# 2-Lead_ECG.net
KiCad netlist of a schematic drawn in EAGLE
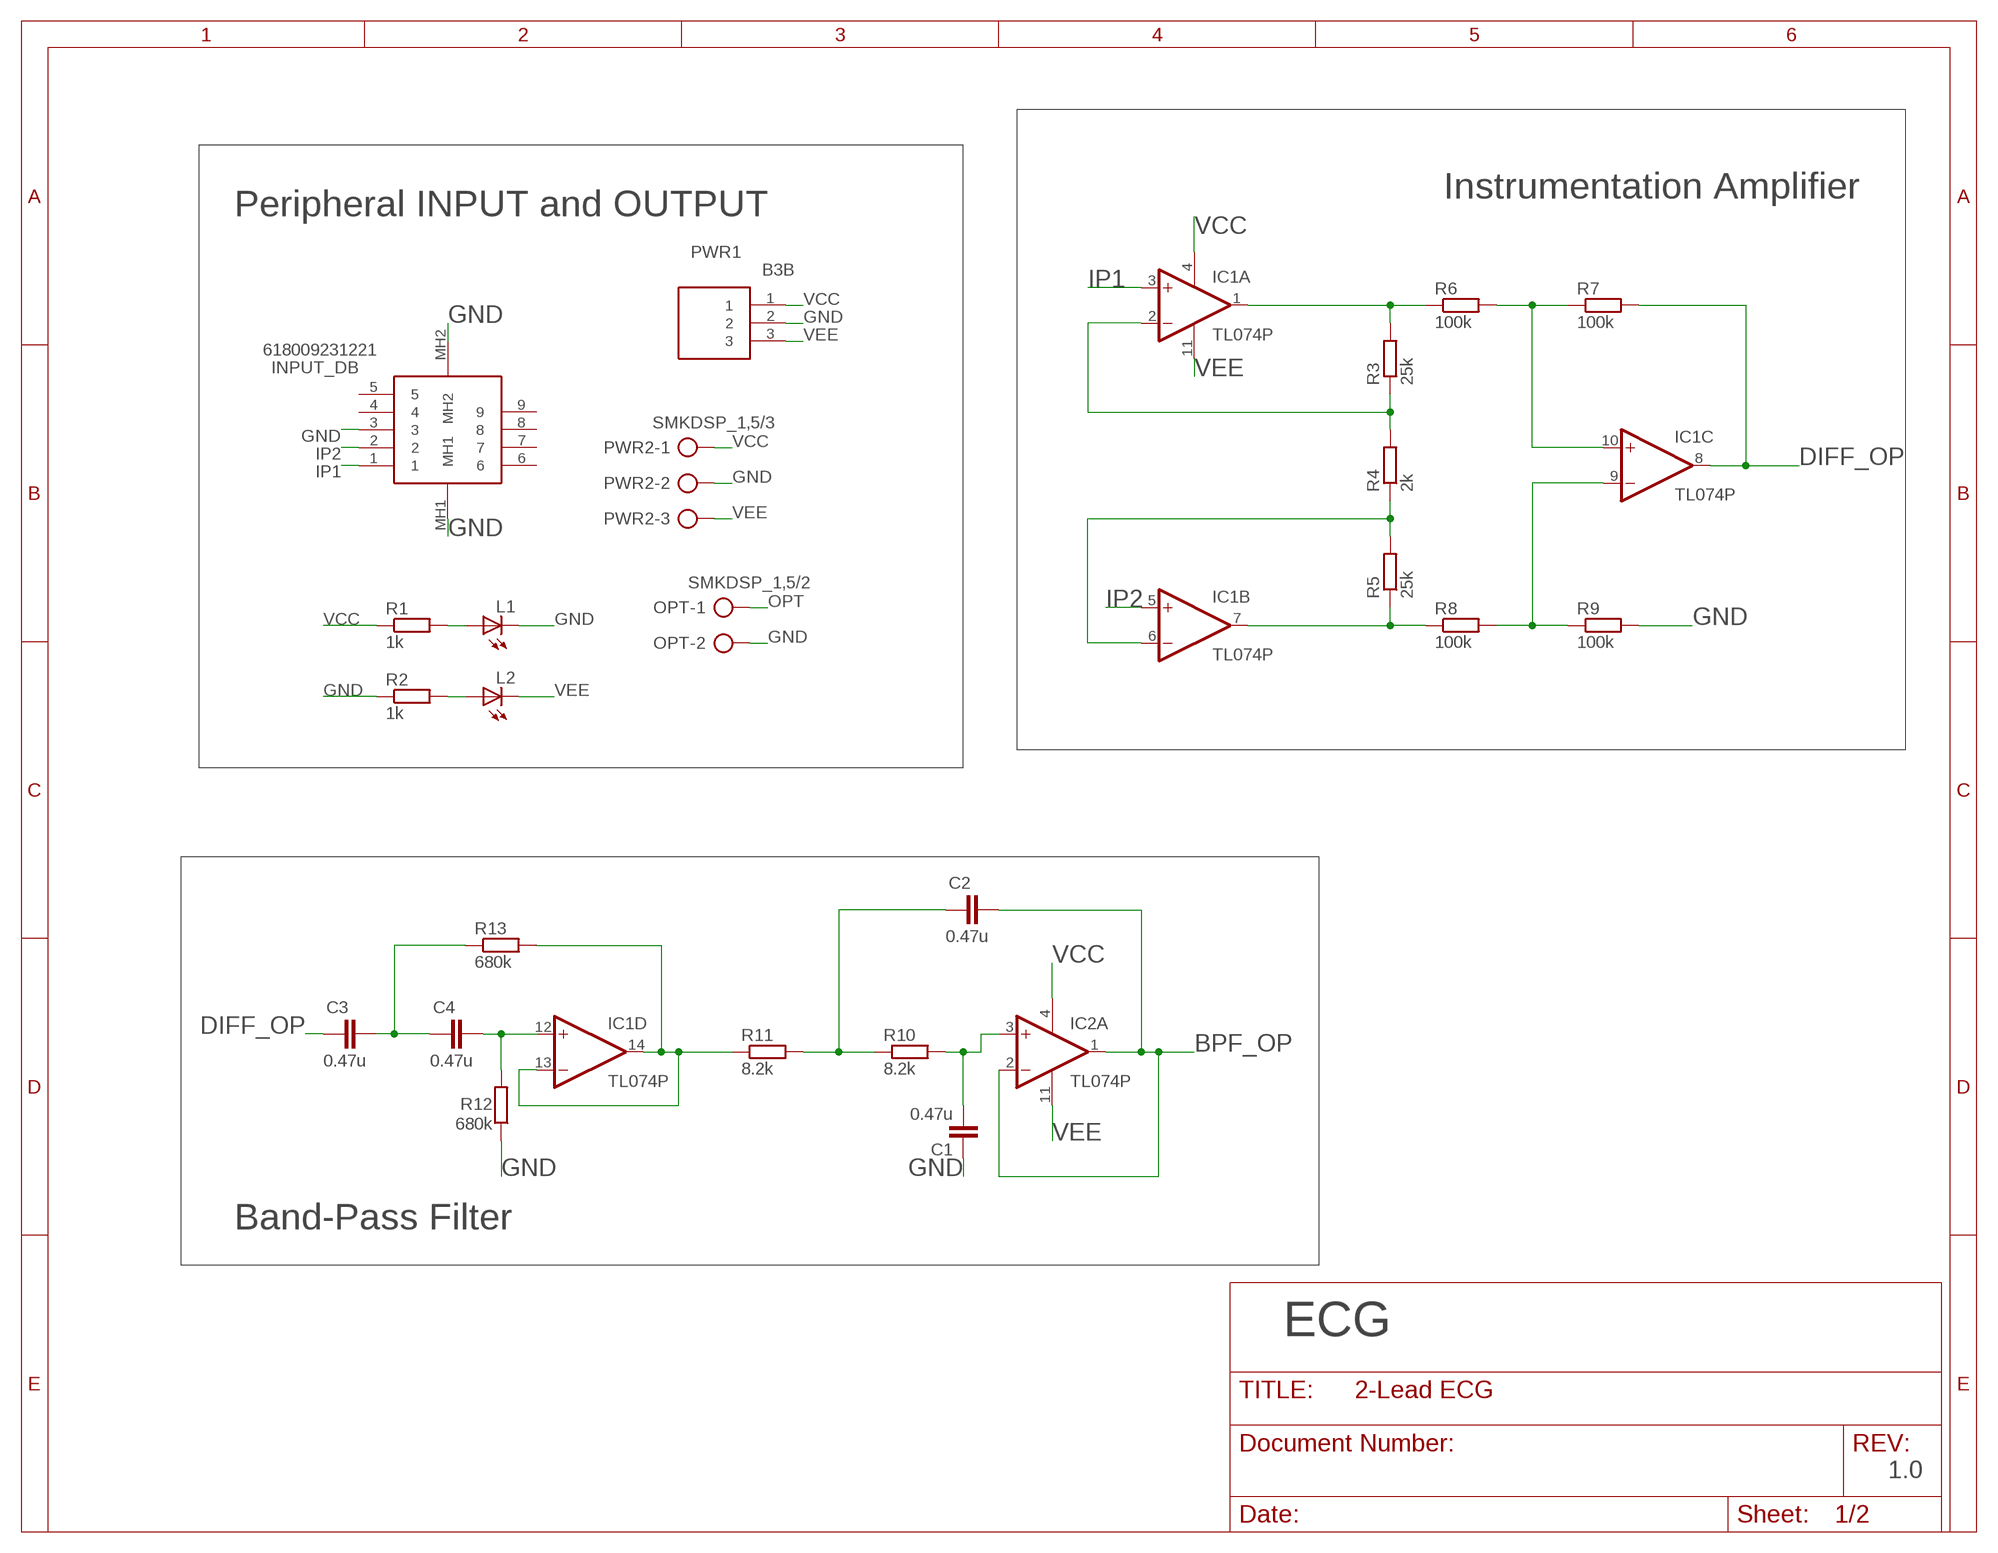
[diagram p0: schematic, sheet 1]
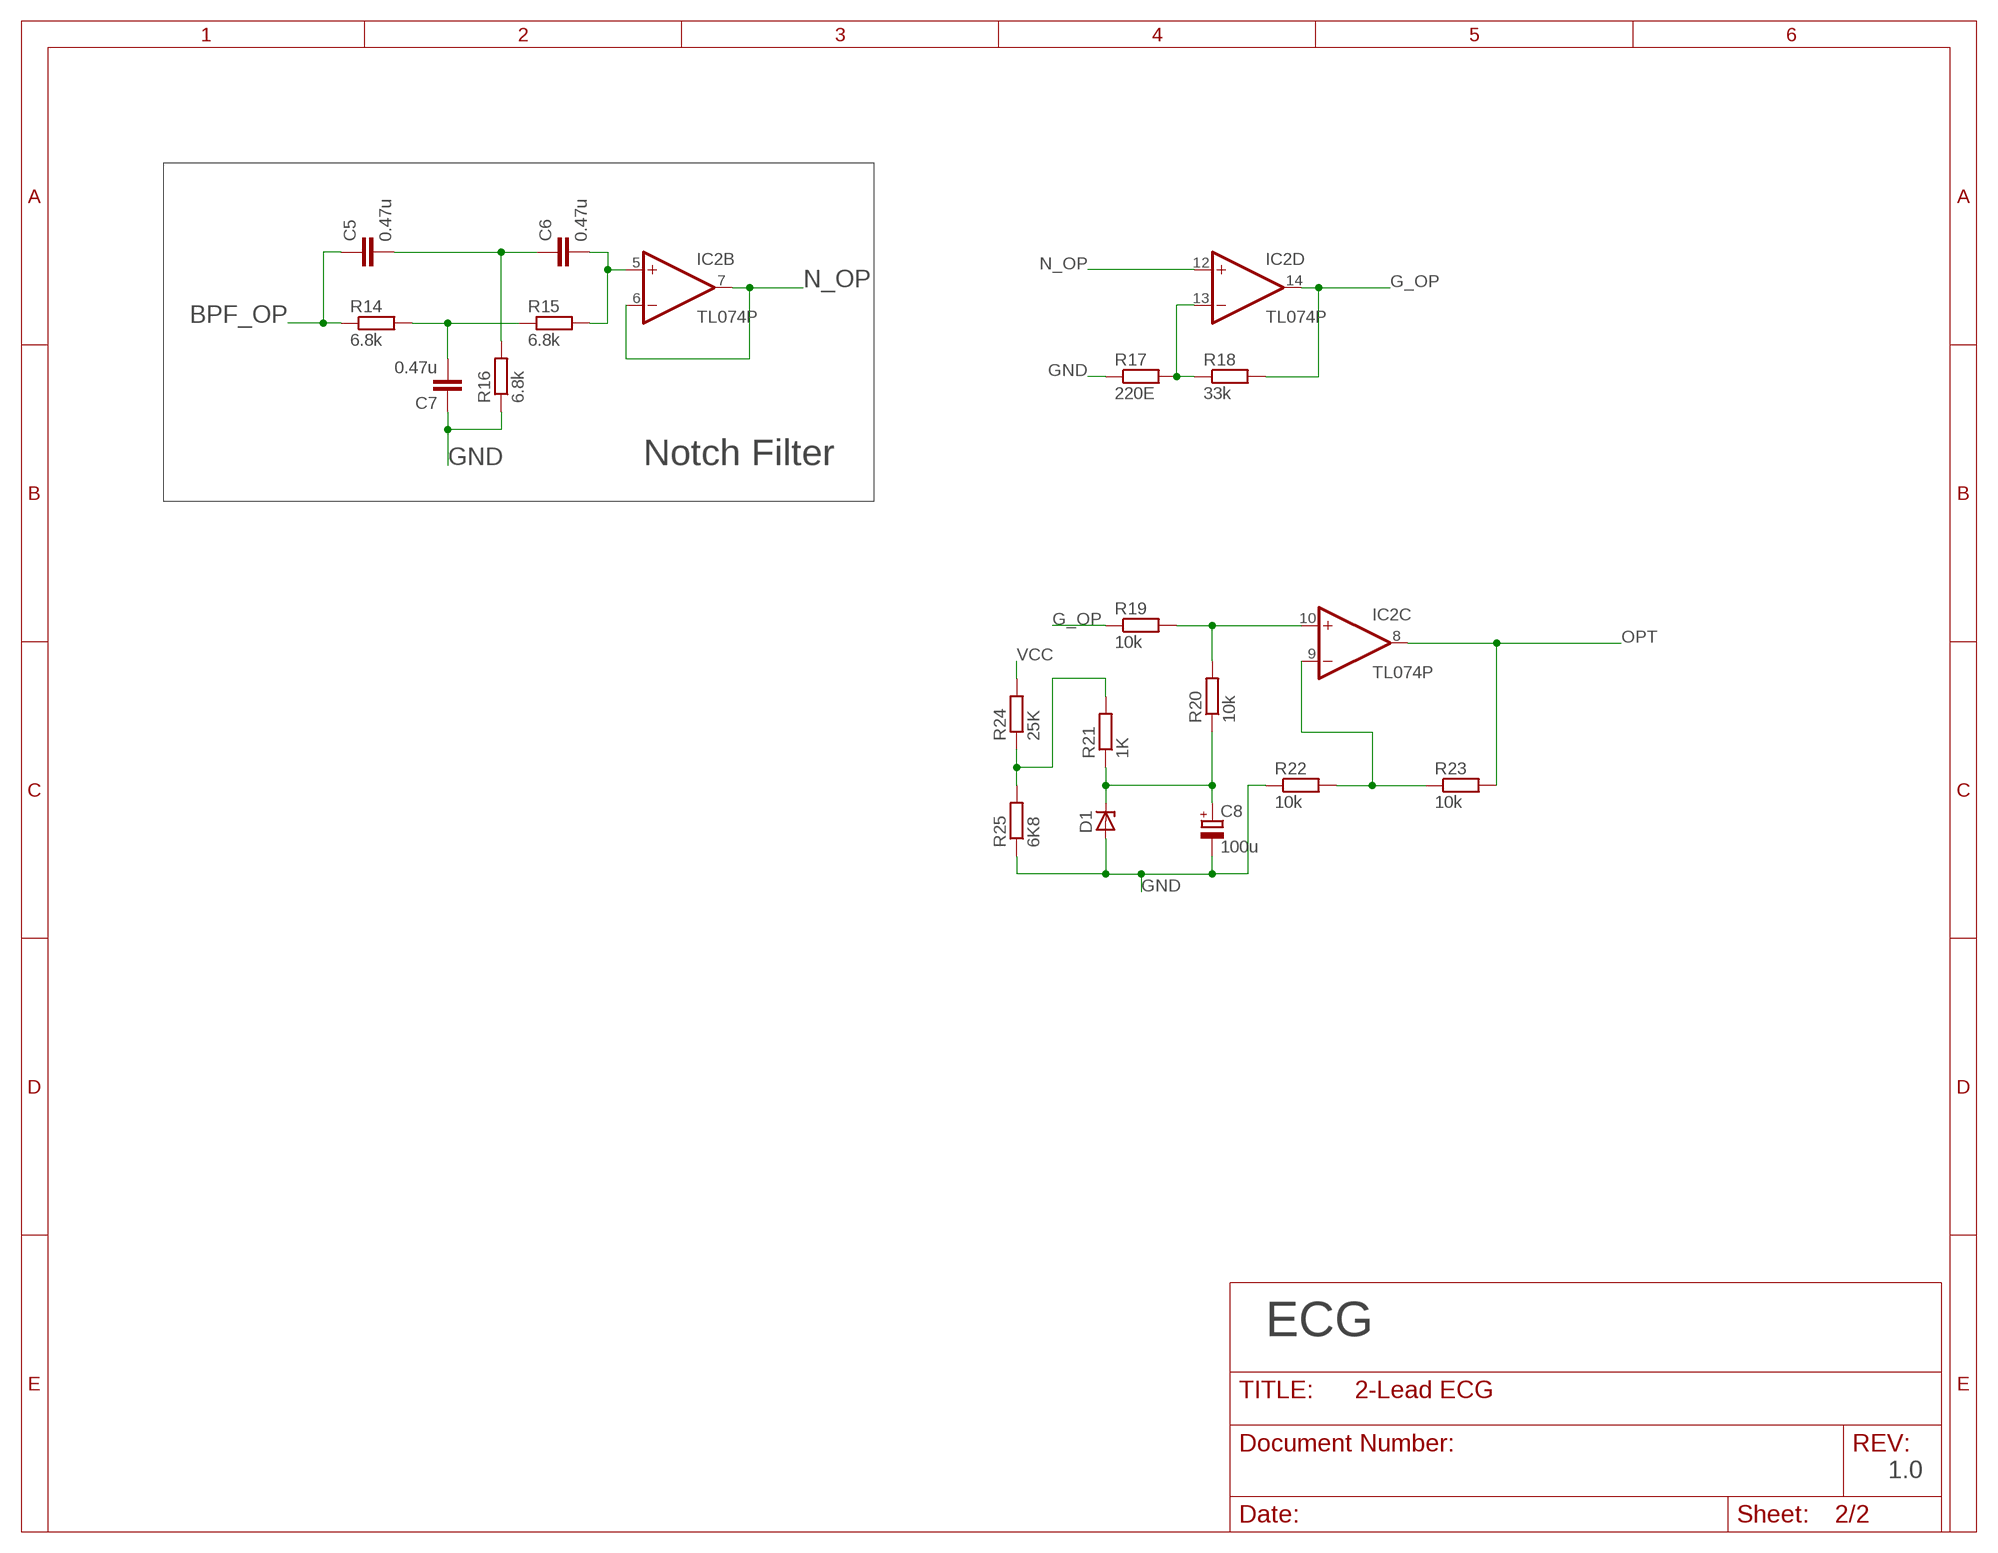
[diagram p1: schematic, sheet 2]

(export (version "E")
  (design (tool "Eeschema 10.0.6"))
  (components
    (comp (ref "C1")
      (value "0.47u")
      (footprint "eagle-import:C050-025X075")
      (libsource (lib "eagle-import") (part "C-EU050-025X075"))
    )
    (comp (ref "C2")
      (value "0.47u")
      (footprint "eagle-import:C050-025X075")
      (libsource (lib "eagle-import") (part "C-EU050-025X075"))
    )
    (comp (ref "C3")
      (value "0.47u")
      (footprint "eagle-import:C050-025X075")
      (libsource (lib "eagle-import") (part "C-EU050-025X075"))
    )
    (comp (ref "C4")
      (value "0.47u")
      (footprint "eagle-import:C050-025X075")
      (libsource (lib "eagle-import") (part "C-EU050-025X075"))
    )
    (comp (ref "IC1")
      (value "TL074P")
      (footprint "eagle-import:DIL14")
      (libsource (lib "eagle-import") (part "TL074P"))
    )
    (comp (ref "IC2")
      (value "TL074P")
      (footprint "eagle-import:DIL14")
      (libsource (lib "eagle-import") (part "TL074P"))
    )
    (comp (ref "INPUT_DB")
      (value "618009231221")
      (footprint "eagle-import:618009231221")
      (fields (field (name "MOUSER_PART_NUMBER") "710-618009231221"))
      (libsource (lib "eagle-import") (part "618009231221"))
    )
    (comp (ref "L1")
      (value "LED3MM")
      (footprint "eagle-import:LED3MM")
      (libsource (lib "eagle-import") (part "LED3MM"))
    )
    (comp (ref "L2")
      (value "LED3MM")
      (footprint "eagle-import:LED3MM")
      (libsource (lib "eagle-import") (part "LED3MM"))
    )
    (comp (ref "OPT")
      (value "SMKDSP_1,5/2")
      (footprint "eagle-import:SMKDSP_1,5_2")
      (fields (field (name "MF") "FARNELL") (field (name "MPN") "1733570"))
      (libsource (lib "eagle-import") (part "SMKDSP_1,5/2"))
    )
    (comp (ref "PWR1")
      (value "B3B")
      (footprint "eagle-import:SHDR3W64P0X250_1X3_1000X380X60")
      (fields (field (name "ARROW_PART_NUMBER") "B3B-EH-A (LF) (SN)"))
      (libsource (lib "eagle-import") (part "B3B-EH-A__LF___SN_"))
    )
    (comp (ref "PWR2")
      (value "SMKDSP_1,5/3")
      (footprint "eagle-import:SMKDSP_1,5_3")
      (fields (field (name "MF") "FARNELL") (field (name "MPN") "1733583"))
      (libsource (lib "eagle-import") (part "SMKDSP_1,5/3"))
    )
    (comp (ref "R1")
      (value "1k")
      (footprint "eagle-import:0207_10")
      (libsource (lib "eagle-import") (part "R-EU_0207/10"))
    )
    (comp (ref "R2")
      (value "1k")
      (footprint "eagle-import:0207_10")
      (libsource (lib "eagle-import") (part "R-EU_0207/10"))
    )
    (comp (ref "R3")
      (value "25k")
      (footprint "eagle-import:0204V")
      (libsource (lib "eagle-import") (part "R-EU_0204/2V"))
    )
    (comp (ref "R4")
      (value "2k")
      (footprint "eagle-import:0207_10")
      (libsource (lib "eagle-import") (part "R-EU_0207/10"))
    )
    (comp (ref "R5")
      (value "25k")
      (footprint "eagle-import:0204V")
      (libsource (lib "eagle-import") (part "R-EU_0204/2V"))
    )
    (comp (ref "R6")
      (value "100k")
      (footprint "eagle-import:0207_10")
      (libsource (lib "eagle-import") (part "R-EU_0207/10"))
    )
    (comp (ref "R7")
      (value "100k")
      (footprint "eagle-import:0207_10")
      (libsource (lib "eagle-import") (part "R-EU_0207/10"))
    )
    (comp (ref "R8")
      (value "100k")
      (footprint "eagle-import:0207_10")
      (libsource (lib "eagle-import") (part "R-EU_0207/10"))
    )
    (comp (ref "R9")
      (value "100k")
      (footprint "eagle-import:0207_10")
      (libsource (lib "eagle-import") (part "R-EU_0207/10"))
    )
    (comp (ref "R10")
      (value "8.2k")
      (footprint "eagle-import:0207_10")
      (libsource (lib "eagle-import") (part "R-EU_0207/10"))
    )
    (comp (ref "R11")
      (value "8.2k")
      (footprint "eagle-import:0207_10")
      (libsource (lib "eagle-import") (part "R-EU_0207/10"))
    )
    (comp (ref "R12")
      (value "680k")
      (footprint "eagle-import:0207_10")
      (libsource (lib "eagle-import") (part "R-EU_0207/10"))
    )
    (comp (ref "R13")
      (value "680k")
      (footprint "eagle-import:0207_10")
      (libsource (lib "eagle-import") (part "R-EU_0207/10"))
    )
    (comp (ref "C5")
      (value "0.47u")
      (footprint "eagle-import:C050-025X075")
      (libsource (lib "eagle-import") (part "C-EU050-025X075"))
    )
    (comp (ref "C6")
      (value "0.47u")
      (footprint "eagle-import:C050-025X075")
      (libsource (lib "eagle-import") (part "C-EU050-025X075"))
    )
    (comp (ref "C7")
      (value "0.47u")
      (footprint "eagle-import:C050-025X075")
      (libsource (lib "eagle-import") (part "C-EU050-025X075"))
    )
    (comp (ref "C8")
      (value "100u")
      (footprint "eagle-import:E2,5-5")
      (libsource (lib "eagle-import") (part "CPOL-EUE2.5-5"))
    )
    (comp (ref "D1")
      (value "ZENER-DIODEC1702-15")
      (footprint "eagle-import:C1702-15")
      (libsource (lib "eagle-import") (part "ZENER-DIODEC1702-15"))
    )
    (comp (ref "R14")
      (value "6.8k")
      (footprint "eagle-import:0207_10")
      (libsource (lib "eagle-import") (part "R-EU_0207/10"))
    )
    (comp (ref "R15")
      (value "6.8k")
      (footprint "eagle-import:0207_10")
      (libsource (lib "eagle-import") (part "R-EU_0207/10"))
    )
    (comp (ref "R16")
      (value "6.8k")
      (footprint "eagle-import:0207_10")
      (libsource (lib "eagle-import") (part "R-EU_0207/10"))
    )
    (comp (ref "R17")
      (value "220E")
      (footprint "eagle-import:0204V")
      (libsource (lib "eagle-import") (part "R-EU_0204/2V"))
    )
    (comp (ref "R18")
      (value "33k")
      (footprint "eagle-import:0204V")
      (libsource (lib "eagle-import") (part "R-EU_0204/2V"))
    )
    (comp (ref "R19")
      (value "10k")
      (footprint "eagle-import:0204V")
      (libsource (lib "eagle-import") (part "R-EU_0204/2V"))
    )
    (comp (ref "R20")
      (value "10k")
      (footprint "eagle-import:0204V")
      (libsource (lib "eagle-import") (part "R-EU_0204/2V"))
    )
    (comp (ref "R21")
      (value "1K")
      (footprint "eagle-import:0207_10")
      (libsource (lib "eagle-import") (part "R-EU_0207/10"))
    )
    (comp (ref "R22")
      (value "10k")
      (footprint "eagle-import:0204V")
      (libsource (lib "eagle-import") (part "R-EU_0204/2V"))
    )
    (comp (ref "R23")
      (value "10k")
      (footprint "eagle-import:0204V")
      (libsource (lib "eagle-import") (part "R-EU_0204/2V"))
    )
    (comp (ref "R24")
      (value "25K")
      (footprint "eagle-import:0207_10")
      (libsource (lib "eagle-import") (part "R-EU_0207/10"))
    )
    (comp (ref "R25")
      (value "6K8")
      (footprint "eagle-import:0207_10")
      (libsource (lib "eagle-import") (part "R-EU_0207/10"))
    )
  )
  (nets
    (net (code "1") (name "BPF_OP") (class "Default")
      (node (ref "C2") (pin "2") (pinfunction "2_2") (pintype "passive"))
      (node (ref "C5") (pin "1") (pinfunction "1_1") (pintype "passive"))
      (node (ref "IC2") (pin "1") (pinfunction "OUT_1") (pintype "output"))
      (node (ref "IC2") (pin "2") (pinfunction "-IN_2") (pintype "input"))
      (node (ref "R14") (pin "1") (pinfunction "1_1") (pintype "passive"))
    )
    (net (code "2") (name "DIFF_OP") (class "Default")
      (node (ref "C3") (pin "1") (pinfunction "1_1") (pintype "passive"))
      (node (ref "IC1") (pin "8") (pinfunction "OUT_8") (pintype "output"))
      (node (ref "R7") (pin "2") (pinfunction "2_2") (pintype "passive"))
    )
    (net (code "3") (name "GND") (class "Default")
      (node (ref "C1") (pin "1") (pinfunction "1_1") (pintype "passive"))
      (node (ref "C7") (pin "1") (pinfunction "1_1") (pintype "passive"))
      (node (ref "C8") (pin "-") (pinfunction "-_-") (pintype "passive"))
      (node (ref "D1") (pin "A") (pinfunction "A_A") (pintype "passive"))
      (node (ref "INPUT_DB") (pin "3") (pinfunction "3_3") (pintype "bidirectional"))
      (node (ref "INPUT_DB") (pin "MH1") (pinfunction "MH1_MH1") (pintype "bidirectional"))
      (node (ref "INPUT_DB") (pin "MH2") (pinfunction "MH2_MH2") (pintype "bidirectional"))
      (node (ref "L1") (pin "K") (pinfunction "C_K") (pintype "passive"))
      (node (ref "OPT") (pin "2") (pinfunction "KL_2") (pintype "passive"))
      (node (ref "PWR1") (pin "2") (pinfunction "2_2") (pintype "bidirectional"))
      (node (ref "PWR2") (pin "2") (pinfunction "KL_2") (pintype "passive"))
      (node (ref "R12") (pin "1") (pinfunction "1_1") (pintype "passive"))
      (node (ref "R16") (pin "1") (pinfunction "1_1") (pintype "passive"))
      (node (ref "R17") (pin "1") (pinfunction "1_1") (pintype "passive"))
      (node (ref "R2") (pin "1") (pinfunction "1_1") (pintype "passive"))
      (node (ref "R22") (pin "1") (pinfunction "1_1") (pintype "passive"))
      (node (ref "R25") (pin "1") (pinfunction "1_1") (pintype "passive"))
      (node (ref "R9") (pin "2") (pinfunction "2_2") (pintype "passive"))
    )
    (net (code "4") (name "G_OP") (class "Default")
      (node (ref "IC2") (pin "14") (pinfunction "OUT_14") (pintype "output"))
      (node (ref "R18") (pin "2") (pinfunction "2_2") (pintype "passive"))
      (node (ref "R19") (pin "1") (pinfunction "1_1") (pintype "passive"))
    )
    (net (code "5") (name "IP1") (class "Default")
      (node (ref "IC1") (pin "3") (pinfunction "+IN_3") (pintype "input"))
      (node (ref "INPUT_DB") (pin "1") (pinfunction "1_1") (pintype "bidirectional"))
    )
    (net (code "6") (name "IP2") (class "Default")
      (node (ref "IC1") (pin "5") (pinfunction "+IN_5") (pintype "input"))
      (node (ref "INPUT_DB") (pin "2") (pinfunction "2_2") (pintype "bidirectional"))
    )
    (net (code "7") (name "N_OP") (class "Default")
      (node (ref "IC2") (pin "12") (pinfunction "+IN_12") (pintype "input"))
      (node (ref "IC2") (pin "6") (pinfunction "-IN_6") (pintype "input"))
      (node (ref "IC2") (pin "7") (pinfunction "OUT_7") (pintype "output"))
    )
    (net (code "8") (name "Net-(C2-Pad1)") (class "Default")
      (node (ref "C2") (pin "1") (pinfunction "1_1") (pintype "passive"))
      (node (ref "R10") (pin "1") (pinfunction "1_1") (pintype "passive"))
      (node (ref "R11") (pin "2") (pinfunction "2_2") (pintype "passive"))
    )
    (net (code "9") (name "Net-(C3-Pad2)") (class "Default")
      (node (ref "C3") (pin "2") (pinfunction "2_2") (pintype "passive"))
      (node (ref "C4") (pin "1") (pinfunction "1_1") (pintype "passive"))
      (node (ref "R13") (pin "1") (pinfunction "1_1") (pintype "passive"))
    )
    (net (code "10") (name "Net-(C5-Pad2)") (class "Default")
      (node (ref "C5") (pin "2") (pinfunction "2_2") (pintype "passive"))
      (node (ref "C6") (pin "1") (pinfunction "1_1") (pintype "passive"))
      (node (ref "R16") (pin "2") (pinfunction "2_2") (pintype "passive"))
    )
    (net (code "11") (name "Net-(C7-Pad2)") (class "Default")
      (node (ref "C7") (pin "2") (pinfunction "2_2") (pintype "passive"))
      (node (ref "R14") (pin "2") (pinfunction "2_2") (pintype "passive"))
      (node (ref "R15") (pin "1") (pinfunction "1_1") (pintype "passive"))
    )
    (net (code "12") (name "Net-(C8-Pad+)") (class "Default")
      (node (ref "C8") (pin "+") (pinfunction "+_+") (pintype "passive"))
      (node (ref "D1") (pin "C") (pinfunction "C_C") (pintype "passive"))
      (node (ref "R20") (pin "1") (pinfunction "1_1") (pintype "passive"))
      (node (ref "R21") (pin "1") (pinfunction "1_1") (pintype "passive"))
    )
    (net (code "13") (name "Net-(IC1A--IN)") (class "Default")
      (node (ref "IC1") (pin "2") (pinfunction "-IN_2") (pintype "input"))
      (node (ref "R3") (pin "1") (pinfunction "1_1") (pintype "passive"))
      (node (ref "R4") (pin "2") (pinfunction "2_2") (pintype "passive"))
    )
    (net (code "14") (name "Net-(IC1A-OUT)") (class "Default")
      (node (ref "IC1") (pin "1") (pinfunction "OUT_1") (pintype "output"))
      (node (ref "R3") (pin "2") (pinfunction "2_2") (pintype "passive"))
      (node (ref "R6") (pin "1") (pinfunction "1_1") (pintype "passive"))
    )
    (net (code "15") (name "Net-(IC1B--IN)") (class "Default")
      (node (ref "IC1") (pin "6") (pinfunction "-IN_6") (pintype "input"))
      (node (ref "R4") (pin "1") (pinfunction "1_1") (pintype "passive"))
      (node (ref "R5") (pin "2") (pinfunction "2_2") (pintype "passive"))
    )
    (net (code "16") (name "Net-(IC1B-OUT)") (class "Default")
      (node (ref "IC1") (pin "7") (pinfunction "OUT_7") (pintype "output"))
      (node (ref "R5") (pin "1") (pinfunction "1_1") (pintype "passive"))
      (node (ref "R8") (pin "1") (pinfunction "1_1") (pintype "passive"))
    )
    (net (code "17") (name "Net-(IC1C-+IN)") (class "Default")
      (node (ref "IC1") (pin "10") (pinfunction "+IN_10") (pintype "input"))
      (node (ref "R6") (pin "2") (pinfunction "2_2") (pintype "passive"))
      (node (ref "R7") (pin "1") (pinfunction "1_1") (pintype "passive"))
    )
    (net (code "18") (name "Net-(IC1C--IN)") (class "Default")
      (node (ref "IC1") (pin "9") (pinfunction "-IN_9") (pintype "input"))
      (node (ref "R8") (pin "2") (pinfunction "2_2") (pintype "passive"))
      (node (ref "R9") (pin "1") (pinfunction "1_1") (pintype "passive"))
    )
    (net (code "19") (name "Net-(IC1D-+IN)") (class "Default")
      (node (ref "C4") (pin "2") (pinfunction "2_2") (pintype "passive"))
      (node (ref "IC1") (pin "12") (pinfunction "+IN_12") (pintype "input"))
      (node (ref "R12") (pin "2") (pinfunction "2_2") (pintype "passive"))
    )
    (net (code "20") (name "Net-(IC1D--IN)") (class "Default")
      (node (ref "IC1") (pin "13") (pinfunction "-IN_13") (pintype "input"))
      (node (ref "IC1") (pin "14") (pinfunction "OUT_14") (pintype "output"))
      (node (ref "R11") (pin "1") (pinfunction "1_1") (pintype "passive"))
      (node (ref "R13") (pin "2") (pinfunction "2_2") (pintype "passive"))
    )
    (net (code "21") (name "Net-(IC2A-+IN)") (class "Default")
      (node (ref "C1") (pin "2") (pinfunction "2_2") (pintype "passive"))
      (node (ref "IC2") (pin "3") (pinfunction "+IN_3") (pintype "input"))
      (node (ref "R10") (pin "2") (pinfunction "2_2") (pintype "passive"))
    )
    (net (code "22") (name "Net-(IC2B-+IN)") (class "Default")
      (node (ref "C6") (pin "2") (pinfunction "2_2") (pintype "passive"))
      (node (ref "IC2") (pin "5") (pinfunction "+IN_5") (pintype "input"))
      (node (ref "R15") (pin "2") (pinfunction "2_2") (pintype "passive"))
    )
    (net (code "23") (name "Net-(IC2C-+IN)") (class "Default")
      (node (ref "IC2") (pin "10") (pinfunction "+IN_10") (pintype "input"))
      (node (ref "R19") (pin "2") (pinfunction "2_2") (pintype "passive"))
      (node (ref "R20") (pin "2") (pinfunction "2_2") (pintype "passive"))
    )
    (net (code "24") (name "Net-(IC2C--IN)") (class "Default")
      (node (ref "IC2") (pin "9") (pinfunction "-IN_9") (pintype "input"))
      (node (ref "R22") (pin "2") (pinfunction "2_2") (pintype "passive"))
      (node (ref "R23") (pin "1") (pinfunction "1_1") (pintype "passive"))
    )
    (net (code "25") (name "Net-(IC2D--IN)") (class "Default")
      (node (ref "IC2") (pin "13") (pinfunction "-IN_13") (pintype "input"))
      (node (ref "R17") (pin "2") (pinfunction "2_2") (pintype "passive"))
      (node (ref "R18") (pin "1") (pinfunction "1_1") (pintype "passive"))
    )
    (net (code "26") (name "Net-(L1-PadA)") (class "Default")
      (node (ref "L1") (pin "A") (pinfunction "A_A") (pintype "passive"))
      (node (ref "R1") (pin "2") (pinfunction "2_2") (pintype "passive"))
    )
    (net (code "27") (name "Net-(L2-PadA)") (class "Default")
      (node (ref "L2") (pin "A") (pinfunction "A_A") (pintype "passive"))
      (node (ref "R2") (pin "2") (pinfunction "2_2") (pintype "passive"))
    )
    (net (code "28") (name "Net-(R21-Pad2)") (class "Default")
      (node (ref "R21") (pin "2") (pinfunction "2_2") (pintype "passive"))
      (node (ref "R24") (pin "1") (pinfunction "1_1") (pintype "passive"))
      (node (ref "R25") (pin "2") (pinfunction "2_2") (pintype "passive"))
    )
    (net (code "29") (name "OPT") (class "Default")
      (node (ref "IC2") (pin "8") (pinfunction "OUT_8") (pintype "output"))
      (node (ref "OPT") (pin "1") (pinfunction "KL_1") (pintype "passive"))
      (node (ref "R23") (pin "2") (pinfunction "2_2") (pintype "passive"))
    )
    (net (code "30") (name "VCC") (class "Default")
      (node (ref "IC1") (pin "4") (pinfunction "V+_4") (pintype "power_in"))
      (node (ref "IC2") (pin "4") (pinfunction "V+_4") (pintype "power_in"))
      (node (ref "PWR1") (pin "1") (pinfunction "1_1") (pintype "bidirectional"))
      (node (ref "PWR2") (pin "1") (pinfunction "KL_1") (pintype "passive"))
      (node (ref "R1") (pin "1") (pinfunction "1_1") (pintype "passive"))
      (node (ref "R24") (pin "2") (pinfunction "2_2") (pintype "passive"))
    )
    (net (code "31") (name "VEE") (class "Default")
      (node (ref "IC1") (pin "11") (pinfunction "V-_11") (pintype "power_in"))
      (node (ref "IC2") (pin "11") (pinfunction "V-_11") (pintype "power_in"))
      (node (ref "L2") (pin "K") (pinfunction "C_K") (pintype "passive"))
      (node (ref "PWR1") (pin "3") (pinfunction "3_3") (pintype "bidirectional"))
      (node (ref "PWR2") (pin "3") (pinfunction "KL_3") (pintype "passive"))
    )
    (net (code "32") (name "unconnected-(INPUT_DB-Pad4)") (class "Default")
      (node (ref "INPUT_DB") (pin "4") (pinfunction "4_4") (pintype "bidirectional"))
    )
    (net (code "33") (name "unconnected-(INPUT_DB-Pad5)") (class "Default")
      (node (ref "INPUT_DB") (pin "5") (pinfunction "5_5") (pintype "bidirectional"))
    )
    (net (code "34") (name "unconnected-(INPUT_DB-Pad6)") (class "Default")
      (node (ref "INPUT_DB") (pin "6") (pinfunction "6_6") (pintype "bidirectional"))
    )
    (net (code "35") (name "unconnected-(INPUT_DB-Pad7)") (class "Default")
      (node (ref "INPUT_DB") (pin "7") (pinfunction "7_7") (pintype "bidirectional"))
    )
    (net (code "36") (name "unconnected-(INPUT_DB-Pad8)") (class "Default")
      (node (ref "INPUT_DB") (pin "8") (pinfunction "8_8") (pintype "bidirectional"))
    )
    (net (code "37") (name "unconnected-(INPUT_DB-Pad9)") (class "Default")
      (node (ref "INPUT_DB") (pin "9") (pinfunction "9_9") (pintype "bidirectional"))
    )
  )
)
